# battery_box2.net
KiCad netlist of a schematic drawn in EAGLE
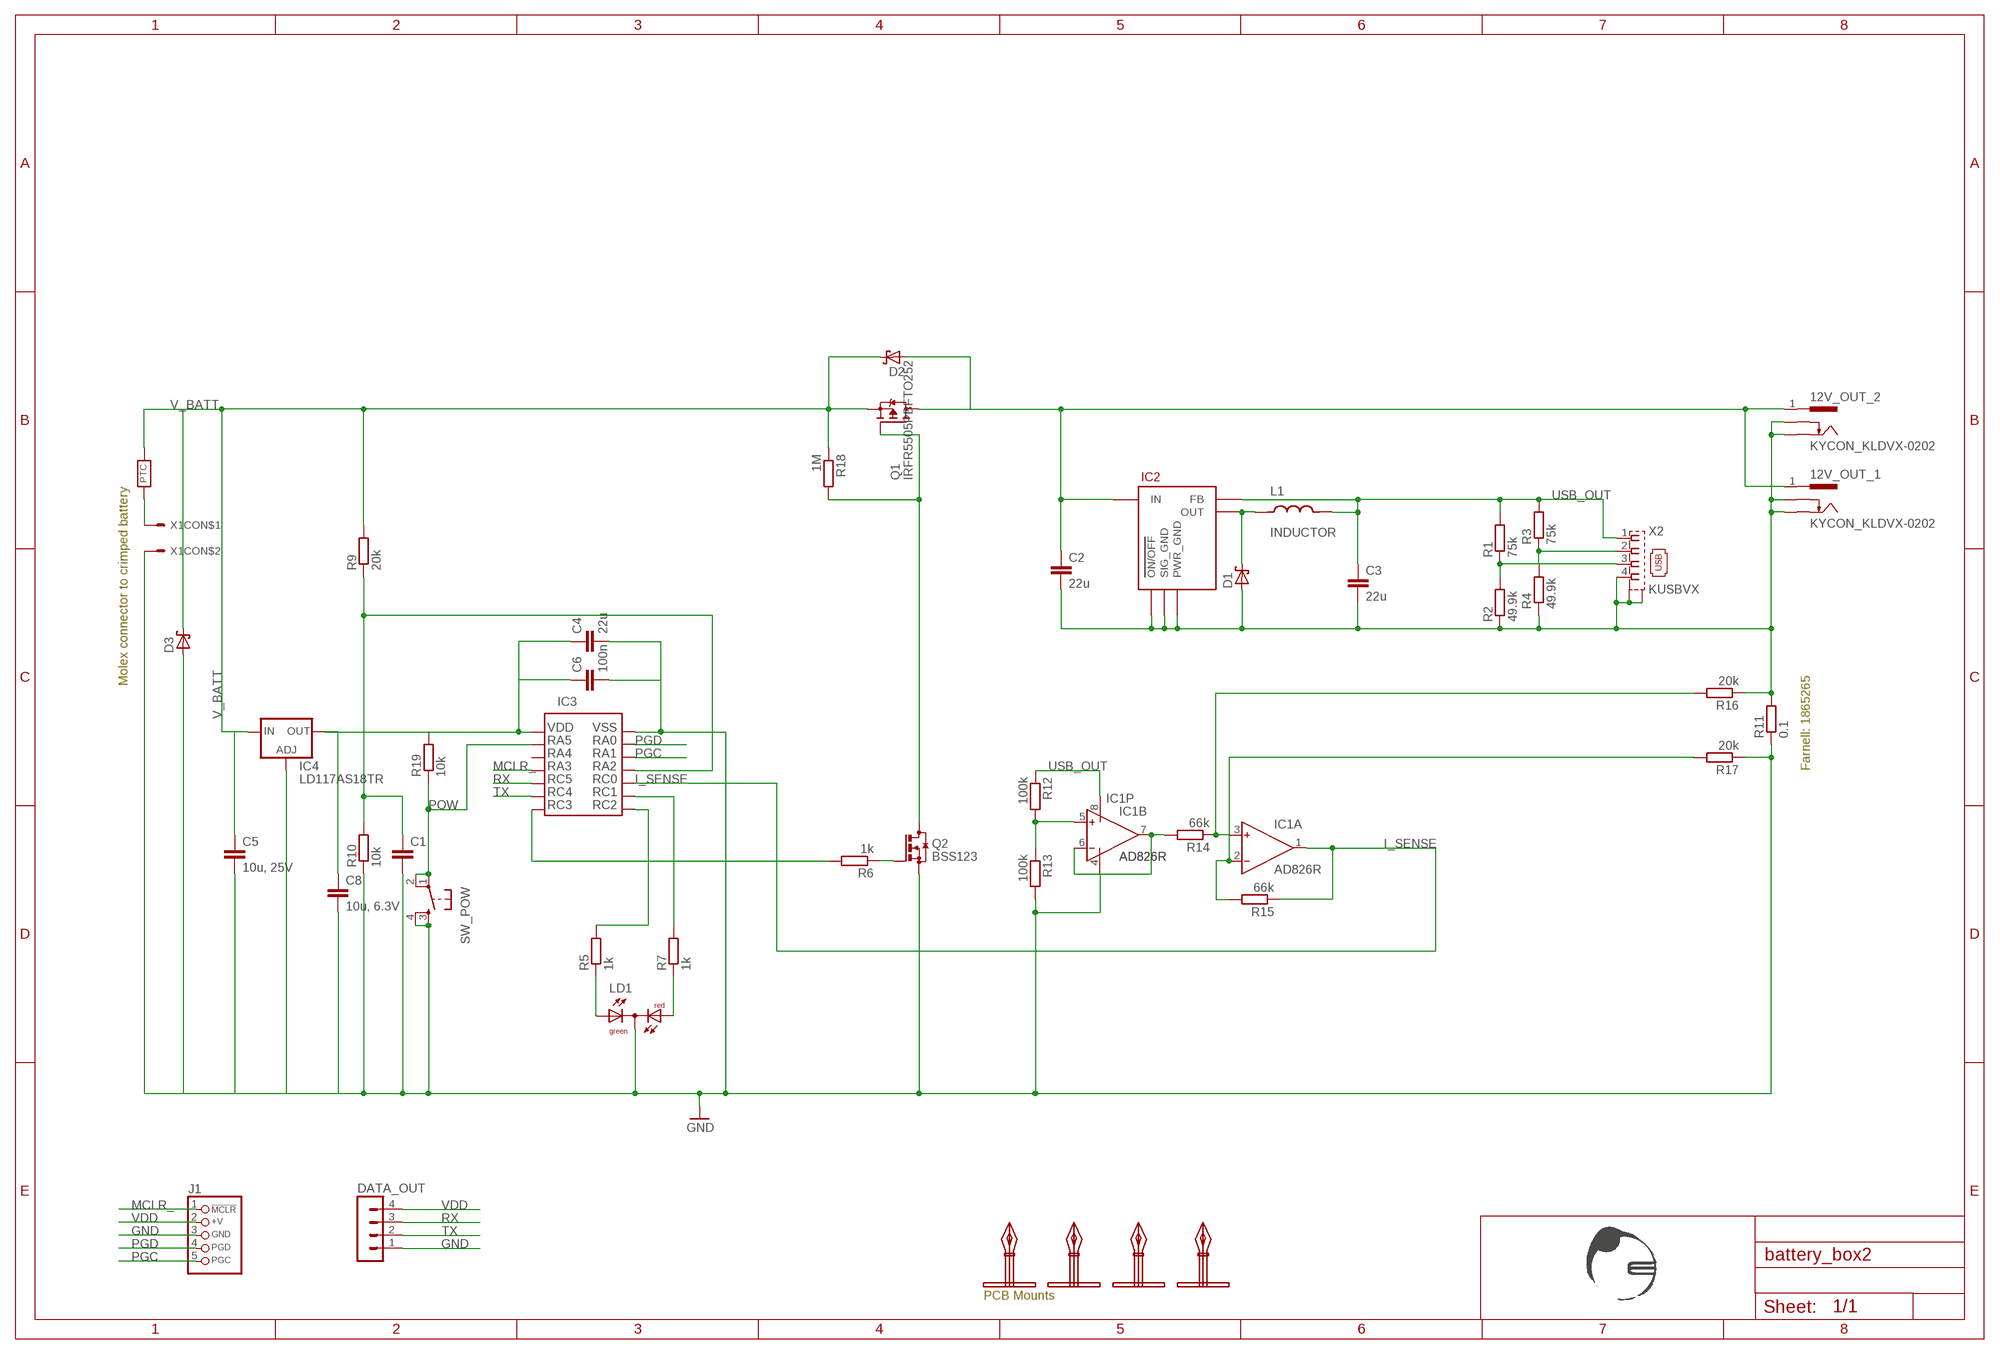
[diagram p0: schematic, sheet 1]

(export (version "E")
  (design (tool "Eeschema 10.0.6"))
  (components
    (comp (ref "12V_OUT_1")
      (value "KYCON_KLDVX-0202")
      (footprint "eagle-import:KYCON_KLVDX_2020_B")
      (libsource (lib "eagle-import") (part "KYCON_KLDVX-0202"))
    )
    (comp (ref "12V_OUT_2")
      (value "KYCON_KLDVX-0202")
      (footprint "eagle-import:KYCON_KLVDX_2020_B")
      (libsource (lib "eagle-import") (part "KYCON_KLDVX-0202"))
    )
    (comp (ref "C1")
      (value "C-EUC0805")
      (footprint "eagle-import:C0805@1")
      (libsource (lib "eagle-import") (part "C-EUC0805"))
    )
    (comp (ref "C2")
      (value "22u")
      (footprint "eagle-import:C0805@1")
      (libsource (lib "eagle-import") (part "C-EUC0805"))
    )
    (comp (ref "C3")
      (value "22u")
      (footprint "eagle-import:C0805@1")
      (libsource (lib "eagle-import") (part "C-EUC0805"))
    )
    (comp (ref "C4")
      (value "22u")
      (footprint "eagle-import:C0805@1")
      (libsource (lib "eagle-import") (part "C-EUC0805"))
    )
    (comp (ref "C5")
      (value "10u, 25V")
      (footprint "eagle-import:C1210")
      (libsource (lib "eagle-import") (part "C-EUC1210"))
    )
    (comp (ref "C6")
      (value "100n")
      (footprint "eagle-import:C0805")
      (libsource (lib "eagle-import") (part "resistor_C-EUC0805"))
    )
    (comp (ref "C8")
      (value "10u, 6.3V")
      (footprint "eagle-import:C0805@1")
      (libsource (lib "eagle-import") (part "C-EUC0805"))
    )
    (comp (ref "D1")
      (value "SCHOTTKY-DIODESMD")
      (footprint "eagle-import:SMB")
      (libsource (lib "eagle-import") (part "SCHOTTKY-DIODESMD"))
    )
    (comp (ref "D2")
      (value "SCHOTTKY-DIODESMC")
      (footprint "eagle-import:SMC")
      (libsource (lib "eagle-import") (part "SCHOTTKY-DIODESMC"))
    )
    (comp (ref "D3")
      (value "SCHOTTKY-DIODESMC")
      (footprint "eagle-import:SMC")
      (libsource (lib "eagle-import") (part "SCHOTTKY-DIODESMC"))
    )
    (comp (ref "DATA_OUT")
      (value "MA04-1")
      (footprint "eagle-import:MA04-1")
      (libsource (lib "eagle-import") (part "MA04-1"))
    )
    (comp (ref "IC1")
      (value "AD826R")
      (footprint "eagle-import:SO8")
      (libsource (lib "eagle-import") (part "AD826R"))
    )
    (comp (ref "IC2")
      (value "LM2574")
      (footprint "eagle-import:SO14W")
      (libsource (lib "eagle-import") (part "LM2574"))
    )
    (comp (ref "IC3")
      (value "PIC16F1824")
      (footprint "eagle-import:SO-14")
      (libsource (lib "eagle-import") (part "PIC16F1824"))
    )
    (comp (ref "IC4")
      (value "LD117AS18TR")
      (footprint "eagle-import:SOT223")
      (libsource (lib "eagle-import") (part "LD117A?S18TR"))
    )
    (comp (ref "J1")
      (value "CON_HEADER_PRG_PIC_ICSPA")
      (footprint "eagle-import:HEADER_PRG_1X05")
      (libsource (lib "eagle-import") (part "CON_HEADER_PRG_PIC_ICSPA"))
    )
    (comp (ref "L1")
      (value "INDUCTOR")
      (footprint "eagle-import:SMD_INDUCTOR")
      (libsource (lib "eagle-import") (part "INDUCTOR"))
    )
    (comp (ref "LD1")
      (value "DUOLED-RG-C")
      (footprint "eagle-import:DUOLED-C-5MM")
      (libsource (lib "eagle-import") (part "DUOLED-RG-C"))
    )
    (comp (ref "Q1")
      (value "IRFR5505PBFTO252")
      (footprint "eagle-import:TO252")
      (libsource (lib "eagle-import") (part "IRFR5505PBFTO252"))
    )
    (comp (ref "Q2")
      (value "BSS123")
      (footprint "eagle-import:SOT23")
      (libsource (lib "eagle-import") (part "BSS123"))
    )
    (comp (ref "R1")
      (value "75k")
      (footprint "eagle-import:R0805")
      (libsource (lib "eagle-import") (part "R-EU_R0805"))
    )
    (comp (ref "R2")
      (value "49.9k")
      (footprint "eagle-import:R0805")
      (libsource (lib "eagle-import") (part "R-EU_R0805"))
    )
    (comp (ref "R3")
      (value "75k")
      (footprint "eagle-import:R0805")
      (libsource (lib "eagle-import") (part "R-EU_R0805"))
    )
    (comp (ref "R4")
      (value "49.9k")
      (footprint "eagle-import:R0805")
      (libsource (lib "eagle-import") (part "R-EU_R0805"))
    )
    (comp (ref "R5")
      (value "1k")
      (footprint "eagle-import:R0805")
      (libsource (lib "eagle-import") (part "R-EU_R0805"))
    )
    (comp (ref "R6")
      (value "1k")
      (footprint "eagle-import:R0805")
      (libsource (lib "eagle-import") (part "R-EU_R0805"))
    )
    (comp (ref "R7")
      (value "1k")
      (footprint "eagle-import:R0805")
      (libsource (lib "eagle-import") (part "R-EU_R0805"))
    )
    (comp (ref "R9")
      (value "20k")
      (footprint "eagle-import:R0805")
      (libsource (lib "eagle-import") (part "R-EU_R0805"))
    )
    (comp (ref "R10")
      (value "10k")
      (footprint "eagle-import:R0805")
      (libsource (lib "eagle-import") (part "R-EU_R0805"))
    )
    (comp (ref "R11")
      (value "0.1")
      (footprint "eagle-import:R2512")
      (libsource (lib "eagle-import") (part "R-EU_R2512"))
    )
    (comp (ref "R12")
      (value "100k")
      (footprint "eagle-import:R0805")
      (libsource (lib "eagle-import") (part "R-EU_R0805"))
    )
    (comp (ref "R13")
      (value "100k")
      (footprint "eagle-import:R0805")
      (libsource (lib "eagle-import") (part "R-EU_R0805"))
    )
    (comp (ref "R14")
      (value "66k")
      (footprint "eagle-import:R0805")
      (libsource (lib "eagle-import") (part "R-EU_R0805"))
    )
    (comp (ref "R15")
      (value "66k")
      (footprint "eagle-import:R0805")
      (libsource (lib "eagle-import") (part "R-EU_R0805"))
    )
    (comp (ref "R16")
      (value "20k")
      (footprint "eagle-import:R0805")
      (libsource (lib "eagle-import") (part "R-EU_R0805"))
    )
    (comp (ref "R17")
      (value "20k")
      (footprint "eagle-import:R0805")
      (libsource (lib "eagle-import") (part "R-EU_R0805"))
    )
    (comp (ref "R18")
      (value "1M")
      (footprint "eagle-import:R0805")
      (libsource (lib "eagle-import") (part "R-EU_R0805"))
    )
    (comp (ref "R19")
      (value "10k")
      (footprint "eagle-import:R0805")
      (libsource (lib "eagle-import") (part "R-EU_R0805"))
    )
    (comp (ref "SW_POW")
      (value "TAC_SWITCHPTH")
      (footprint "eagle-import:TACTILE-PTH")
      (libsource (lib "eagle-import") (part "TAC_SWITCHPTH"))
    )
    (comp (ref "U$1")
      (value "EQUINOX_LOGO_SMALL")
      (footprint "eagle-import:EQUINOX_LOGO_SMALL")
      (libsource (lib "eagle-import") (part "EQUINOX_LOGO_SMALL"))
    )
    (comp (ref "U$2")
      (value "PTC")
      (footprint "eagle-import:MINISMDC260F")
      (libsource (lib "eagle-import") (part "PTC"))
    )
    (comp (ref "U$5")
      (value "PCB_MOUNT_RICHO")
      (footprint "eagle-import:PCBMOUNT")
      (libsource (lib "eagle-import") (part "PCB_MOUNT_RICHO"))
    )
    (comp (ref "U$6")
      (value "PCB_MOUNT_RICHO")
      (footprint "eagle-import:PCBMOUNT")
      (libsource (lib "eagle-import") (part "PCB_MOUNT_RICHO"))
    )
    (comp (ref "U$7")
      (value "PCB_MOUNT_RICHO")
      (footprint "eagle-import:PCBMOUNT")
      (libsource (lib "eagle-import") (part "PCB_MOUNT_RICHO"))
    )
    (comp (ref "U$8")
      (value "PCB_MOUNT_RICHO")
      (footprint "eagle-import:PCBMOUNT")
      (libsource (lib "eagle-import") (part "PCB_MOUNT_RICHO"))
    )
    (comp (ref "X1")
      (value "CON_MOLEX_39_29_1028")
      (footprint "eagle-import:MOLEX_39_29_1028")
      (libsource (lib "eagle-import") (part "CON_MOLEX_39_29_1028"))
    )
    (comp (ref "X2")
      (value "KUSBVX")
      (footprint "eagle-import:KUSBVX")
      (libsource (lib "eagle-import") (part "KUSBVX"))
    )
  )
  (nets
    (net (code "1") (name "/I_SENSE") (class "Default")
      (node (ref "IC1") (pin "1") (pinfunction "OUT_1") (pintype "output"))
      (node (ref "IC3") (pin "10") (pinfunction "P$10_10") (pintype "bidirectional"))
      (node (ref "R15") (pin "1") (pinfunction "1_1") (pintype "passive"))
    )
    (net (code "2") (name "/MCLR_") (class "Default")
      (node (ref "IC3") (pin "4") (pinfunction "P$4_4") (pintype "bidirectional"))
      (node (ref "J1") (pin "1") (pinfunction "/MCLR_1") (pintype "passive"))
    )
    (net (code "3") (name "/PGC") (class "Default")
      (node (ref "IC3") (pin "12") (pinfunction "P$12_12") (pintype "bidirectional"))
      (node (ref "J1") (pin "5") (pinfunction "PGC_5") (pintype "passive"))
    )
    (net (code "4") (name "/PGD") (class "Default")
      (node (ref "IC3") (pin "13") (pinfunction "P$13_13") (pintype "bidirectional"))
      (node (ref "J1") (pin "4") (pinfunction "PGD_4") (pintype "passive"))
    )
    (net (code "5") (name "/POW") (class "Default")
      (node (ref "IC3") (pin "2") (pinfunction "P$2_2") (pintype "bidirectional"))
      (node (ref "R19") (pin "1") (pinfunction "1_1") (pintype "passive"))
      (node (ref "SW_POW") (pin "1") (pinfunction "1_1") (pintype "passive"))
      (node (ref "SW_POW") (pin "2") (pinfunction "2_2") (pintype "passive"))
    )
    (net (code "6") (name "/RX") (class "Default")
      (node (ref "DATA_OUT") (pin "3") (pinfunction "3_3") (pintype "passive"))
      (node (ref "IC3") (pin "5") (pinfunction "P$5_5") (pintype "bidirectional"))
    )
    (net (code "7") (name "/TX") (class "Default")
      (node (ref "DATA_OUT") (pin "2") (pinfunction "2_2") (pintype "passive"))
      (node (ref "IC3") (pin "6") (pinfunction "P$6_6") (pintype "bidirectional"))
    )
    (net (code "8") (name "/USB_OUT") (class "Default")
      (node (ref "C3") (pin "1") (pinfunction "1_1") (pintype "passive"))
      (node (ref "IC1") (pin "8") (pinfunction "V+_8") (pintype "power_in"))
      (node (ref "IC2") (pin "3") (pinfunction "FB_3") (pintype "bidirectional"))
      (node (ref "L1") (pin "P$2") (pinfunction "P$2_P$2") (pintype "bidirectional"))
      (node (ref "R1") (pin "2") (pinfunction "2_2") (pintype "passive"))
      (node (ref "R12") (pin "1") (pinfunction "1_1") (pintype "passive"))
      (node (ref "R3") (pin "2") (pinfunction "2_2") (pintype "passive"))
      (node (ref "X2") (pin "1") (pinfunction "1_1") (pintype "passive"))
    )
    (net (code "9") (name "/VDD") (class "Default")
      (node (ref "C4") (pin "1") (pinfunction "1_1") (pintype "passive"))
      (node (ref "C6") (pin "1") (pinfunction "1_1") (pintype "passive"))
      (node (ref "C8") (pin "1") (pinfunction "1_1") (pintype "passive"))
      (node (ref "DATA_OUT") (pin "4") (pinfunction "4_4") (pintype "passive"))
      (node (ref "IC3") (pin "1") (pinfunction "P$1_1") (pintype "bidirectional"))
      (node (ref "IC4") (pin "4") (pinfunction "OUT_4") (pintype "passive"))
      (node (ref "J1") (pin "2") (pinfunction "+V_2") (pintype "passive"))
      (node (ref "R19") (pin "2") (pinfunction "2_2") (pintype "passive"))
    )
    (net (code "10") (name "/V_BATT") (class "Default")
      (node (ref "C5") (pin "1") (pinfunction "1_1") (pintype "passive"))
      (node (ref "D2") (pin "C") (pinfunction "C_C") (pintype "passive"))
      (node (ref "D3") (pin "C") (pinfunction "C_C") (pintype "passive"))
      (node (ref "IC4") (pin "3") (pinfunction "IN_3") (pintype "input"))
      (node (ref "Q1") (pin "2") (pinfunction "S_2") (pintype "passive"))
      (node (ref "R18") (pin "1") (pinfunction "1_1") (pintype "passive"))
      (node (ref "R9") (pin "2") (pinfunction "2_2") (pintype "passive"))
      (node (ref "U$2") (pin "P$2") (pinfunction "P$2_P$2") (pintype "bidirectional"))
    )
    (net (code "11") (name "GND") (class "Default")
      (node (ref "C1") (pin "2") (pinfunction "2_2") (pintype "passive"))
      (node (ref "C4") (pin "2") (pinfunction "2_2") (pintype "passive"))
      (node (ref "C5") (pin "2") (pinfunction "2_2") (pintype "passive"))
      (node (ref "C6") (pin "2") (pinfunction "2_2") (pintype "passive"))
      (node (ref "C8") (pin "2") (pinfunction "2_2") (pintype "passive"))
      (node (ref "D3") (pin "A") (pinfunction "A_A") (pintype "passive"))
      (node (ref "DATA_OUT") (pin "1") (pinfunction "1_1") (pintype "passive"))
      (node (ref "IC1") (pin "4") (pinfunction "V-_4") (pintype "power_in"))
      (node (ref "IC3") (pin "14") (pinfunction "P$14_14") (pintype "bidirectional"))
      (node (ref "IC4") (pin "1") (pinfunction "ADJ_1") (pintype "input"))
      (node (ref "J1") (pin "3") (pinfunction "GND_3") (pintype "passive"))
      (node (ref "LD1") (pin "C") (pinfunction "C_C") (pintype "passive"))
      (node (ref "Q2") (pin "2") (pinfunction "S_2") (pintype "passive"))
      (node (ref "R10") (pin "1") (pinfunction "1_1") (pintype "passive"))
      (node (ref "R11") (pin "1") (pinfunction "1_1") (pintype "passive"))
      (node (ref "R13") (pin "2") (pinfunction "2_2") (pintype "passive"))
      (node (ref "R17") (pin "1") (pinfunction "1_1") (pintype "passive"))
      (node (ref "SW_POW") (pin "3") (pinfunction "3_3") (pintype "passive"))
      (node (ref "SW_POW") (pin "4") (pinfunction "4_4") (pintype "passive"))
      (node (ref "X1") (pin "P$2") (pinfunction "S_P$2") (pintype "passive"))
    )
    (net (code "12") (name "Net-(12V_OUT_1-PAD1)") (class "Default")
      (node (ref "12V_OUT_1") (pin "1") (pinfunction "PAD1_1") (pintype "passive"))
      (node (ref "12V_OUT_2") (pin "1") (pinfunction "PAD1_1") (pintype "passive"))
      (node (ref "C2") (pin "1") (pinfunction "1_1") (pintype "passive"))
      (node (ref "D2") (pin "A") (pinfunction "A_A") (pintype "passive"))
      (node (ref "IC2") (pin "10") (pinfunction "IN_10") (pintype "bidirectional"))
      (node (ref "Q1") (pin "3") (pinfunction "D_3") (pintype "passive"))
    )
    (net (code "13") (name "Net-(12V_OUT_1-PAD2)") (class "Default")
      (node (ref "12V_OUT_1") (pin "2") (pinfunction "PAD2_2") (pintype "passive"))
      (node (ref "12V_OUT_1") (pin "3") (pinfunction "PAD3_3") (pintype "passive"))
      (node (ref "12V_OUT_2") (pin "2") (pinfunction "PAD2_2") (pintype "passive"))
      (node (ref "12V_OUT_2") (pin "3") (pinfunction "PAD3_3") (pintype "passive"))
      (node (ref "C2") (pin "2") (pinfunction "2_2") (pintype "passive"))
      (node (ref "C3") (pin "2") (pinfunction "2_2") (pintype "passive"))
      (node (ref "D1") (pin "A") (pinfunction "A_A") (pintype "passive"))
      (node (ref "IC2") (pin "4") (pinfunction "SIG_GND_4") (pintype "bidirectional"))
      (node (ref "IC2") (pin "5") (pinfunction "ON/OFF_5") (pintype "bidirectional"))
      (node (ref "IC2") (pin "6") (pinfunction "PWR_GND_6") (pintype "bidirectional"))
      (node (ref "R11") (pin "2") (pinfunction "2_2") (pintype "passive"))
      (node (ref "R16") (pin "1") (pinfunction "1_1") (pintype "passive"))
      (node (ref "R2") (pin "1") (pinfunction "1_1") (pintype "passive"))
      (node (ref "R4") (pin "1") (pinfunction "1_1") (pintype "passive"))
      (node (ref "X2") (pin "4") (pinfunction "4_4") (pintype "passive"))
      (node (ref "X2") (pin "M1") (pinfunction "S1_M1") (pintype "passive"))
      (node (ref "X2") (pin "M2") (pinfunction "S2_M2") (pintype "passive"))
    )
    (net (code "14") (name "Net-(IC1A-IN+)") (class "Default")
      (node (ref "IC1") (pin "3") (pinfunction "IN+_3") (pintype "input"))
      (node (ref "R14") (pin "1") (pinfunction "1_1") (pintype "passive"))
      (node (ref "R16") (pin "2") (pinfunction "2_2") (pintype "passive"))
    )
    (net (code "15") (name "Net-(IC1A-IN-)") (class "Default")
      (node (ref "IC1") (pin "2") (pinfunction "IN-_2") (pintype "input"))
      (node (ref "R15") (pin "2") (pinfunction "2_2") (pintype "passive"))
      (node (ref "R17") (pin "2") (pinfunction "2_2") (pintype "passive"))
    )
    (net (code "16") (name "Net-(IC1B-IN+)") (class "Default")
      (node (ref "IC1") (pin "5") (pinfunction "IN+_5") (pintype "input"))
      (node (ref "R12") (pin "2") (pinfunction "2_2") (pintype "passive"))
      (node (ref "R13") (pin "1") (pinfunction "1_1") (pintype "passive"))
    )
    (net (code "17") (name "Net-(IC1B-IN-)") (class "Default")
      (node (ref "IC1") (pin "6") (pinfunction "IN-_6") (pintype "input"))
      (node (ref "IC1") (pin "7") (pinfunction "OUT_7") (pintype "output"))
      (node (ref "R14") (pin "2") (pinfunction "2_2") (pintype "passive"))
    )
    (net (code "18") (name "Net-(IC2-OUT)") (class "Default")
      (node (ref "D1") (pin "C") (pinfunction "C_C") (pintype "passive"))
      (node (ref "IC2") (pin "12") (pinfunction "OUT_12") (pintype "bidirectional"))
      (node (ref "L1") (pin "P$1") (pinfunction "P$1_P$1") (pintype "bidirectional"))
    )
    (net (code "19") (name "Net-(IC3-P$7)") (class "Default")
      (node (ref "IC3") (pin "7") (pinfunction "P$7_7") (pintype "bidirectional"))
      (node (ref "R6") (pin "2") (pinfunction "2_2") (pintype "passive"))
    )
    (net (code "20") (name "Net-(IC3-P$8)") (class "Default")
      (node (ref "IC3") (pin "8") (pinfunction "P$8_8") (pintype "bidirectional"))
      (node (ref "R5") (pin "2") (pinfunction "2_2") (pintype "passive"))
    )
    (net (code "21") (name "Net-(IC3-P$9)") (class "Default")
      (node (ref "IC3") (pin "9") (pinfunction "P$9_9") (pintype "bidirectional"))
      (node (ref "R7") (pin "2") (pinfunction "2_2") (pintype "passive"))
    )
    (net (code "22") (name "Net-(IC3-P$11)") (class "Default")
      (node (ref "C1") (pin "1") (pinfunction "1_1") (pintype "passive"))
      (node (ref "IC3") (pin "11") (pinfunction "P$11_11") (pintype "bidirectional"))
      (node (ref "R10") (pin "2") (pinfunction "2_2") (pintype "passive"))
      (node (ref "R9") (pin "1") (pinfunction "1_1") (pintype "passive"))
    )
    (net (code "23") (name "Net-(LD1-AG)") (class "Default")
      (node (ref "LD1") (pin "AX") (pinfunction "AG_AX") (pintype "passive"))
      (node (ref "R5") (pin "1") (pinfunction "1_1") (pintype "passive"))
    )
    (net (code "24") (name "Net-(LD1-PadAR)") (class "Default")
      (node (ref "LD1") (pin "AR") (pinfunction "AR_AR") (pintype "passive"))
      (node (ref "R7") (pin "1") (pinfunction "1_1") (pintype "passive"))
    )
    (net (code "25") (name "Net-(Q1-G)") (class "Default")
      (node (ref "Q1") (pin "1") (pinfunction "G_1") (pintype "passive"))
      (node (ref "Q2") (pin "3") (pinfunction "D_3") (pintype "passive"))
      (node (ref "R18") (pin "2") (pinfunction "2_2") (pintype "passive"))
    )
    (net (code "26") (name "Net-(Q2-G)") (class "Default")
      (node (ref "Q2") (pin "1") (pinfunction "G_1") (pintype "passive"))
      (node (ref "R6") (pin "1") (pinfunction "1_1") (pintype "passive"))
    )
    (net (code "27") (name "Net-(R1-Pad1)") (class "Default")
      (node (ref "R1") (pin "1") (pinfunction "1_1") (pintype "passive"))
      (node (ref "R2") (pin "2") (pinfunction "2_2") (pintype "passive"))
      (node (ref "X2") (pin "3") (pinfunction "3_3") (pintype "passive"))
    )
    (net (code "28") (name "Net-(R3-Pad1)") (class "Default")
      (node (ref "R3") (pin "1") (pinfunction "1_1") (pintype "passive"))
      (node (ref "R4") (pin "2") (pinfunction "2_2") (pintype "passive"))
      (node (ref "X2") (pin "2") (pinfunction "2_2") (pintype "passive"))
    )
    (net (code "29") (name "Net-(X1A-S)") (class "Default")
      (node (ref "U$2") (pin "P$1") (pinfunction "P$1_P$1") (pintype "bidirectional"))
      (node (ref "X1") (pin "P$1") (pinfunction "S_P$1") (pintype "passive"))
    )
    (net (code "30") (name "unconnected-(IC3-P$3-Pad3)") (class "Default")
      (node (ref "IC3") (pin "3") (pinfunction "P$3_3") (pintype "bidirectional"))
    )
  )
)
